# PowCarbinBoard_Isolation.net
KiCad netlist of a schematic drawn in Altium Designer
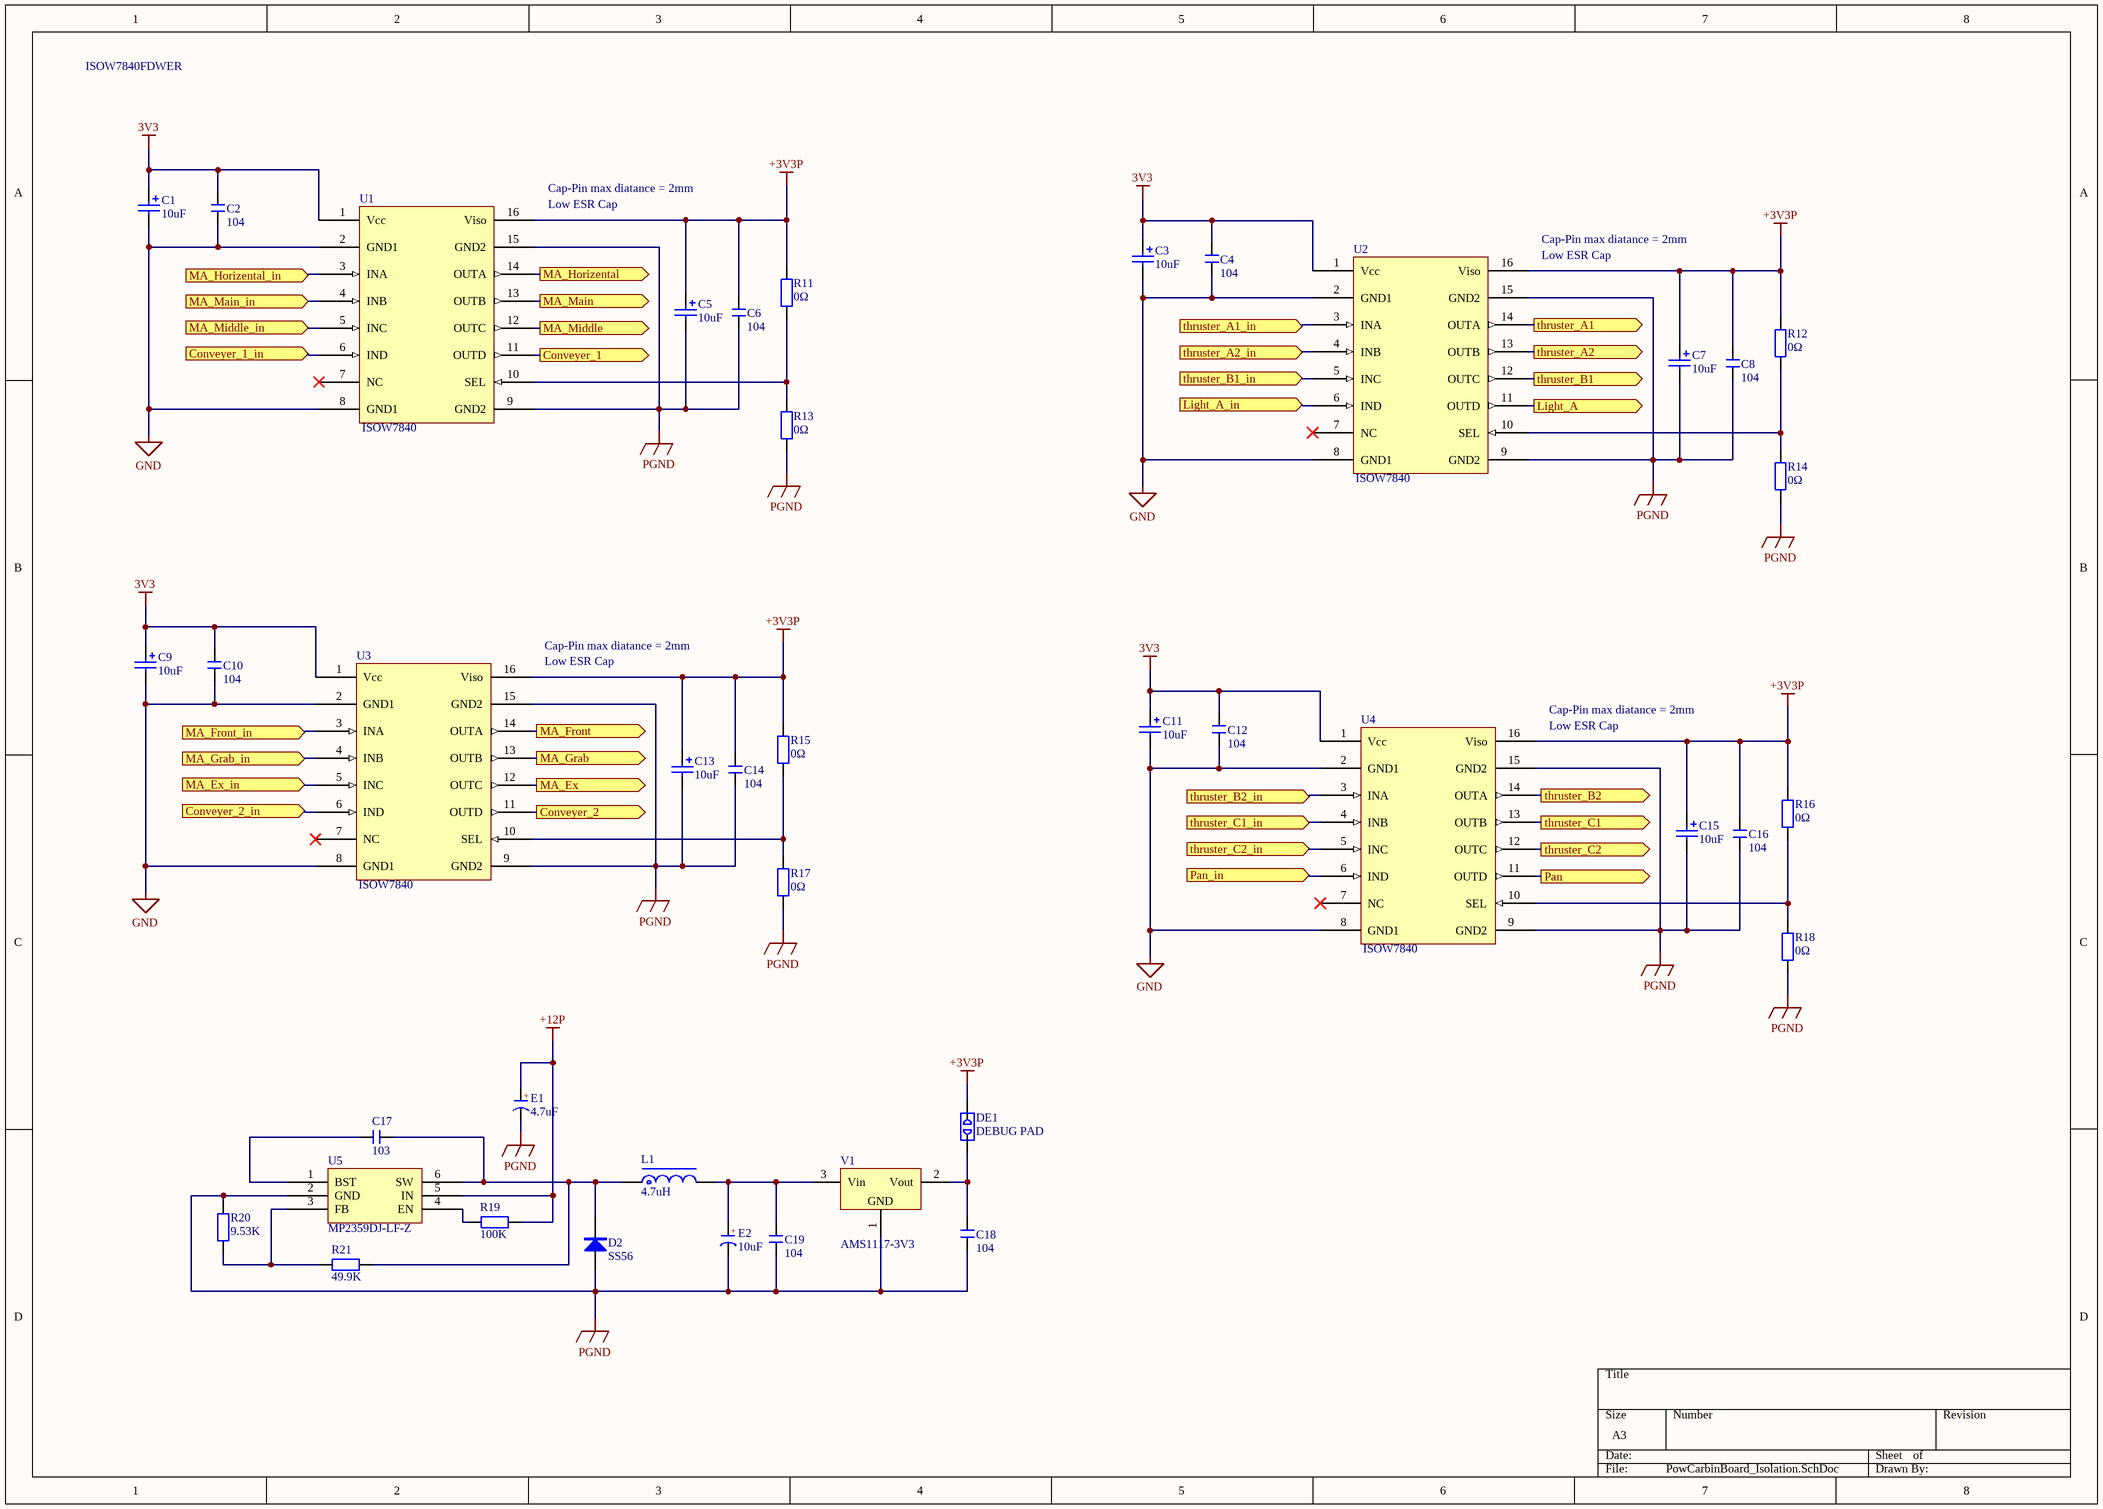
[diagram p0: PowCarbinBoard_Isolation.SchDoc]

(export (version "E")
  (design (tool "Eeschema 10.0.6"))
  (components
    (comp (ref "C1")
      (value "10uF")
      (footprint "CASE-B_3528")
      (description "钽电容")
      (libsource (lib "Miscellaneous Devices LC") (part "3528 100uF (107) 10% 6.3V"))
    )
    (comp (ref "C2")
      (value "104")
      (footprint "C 0603_L")
      (description "无极性贴片电容")
      (fields (field (name "版权归属") "源创客"))
      (libsource (lib "3.1   - 电阻-电容-电感") (part "C"))
    )
    (comp (ref "C3")
      (value "10uF")
      (footprint "CASE-B_3528")
      (description "钽电容")
      (libsource (lib "Miscellaneous Devices LC") (part "3528 100uF (107) 10% 6.3V"))
    )
    (comp (ref "C4")
      (value "104")
      (footprint "C 0603_L")
      (description "无极性贴片电容")
      (fields (field (name "版权归属") "源创客"))
      (libsource (lib "3.1   - 电阻-电容-电感") (part "C"))
    )
    (comp (ref "C5")
      (value "10uF")
      (footprint "CASE-B_3528")
      (description "钽电容")
      (libsource (lib "Miscellaneous Devices LC") (part "3528 100uF (107) 10% 6.3V"))
    )
    (comp (ref "C6")
      (value "104")
      (footprint "C 0603_L")
      (description "无极性贴片电容")
      (fields (field (name "版权归属") "源创客"))
      (libsource (lib "3.1   - 电阻-电容-电感") (part "C"))
    )
    (comp (ref "C7")
      (value "10uF")
      (footprint "CASE-B_3528")
      (description "钽电容")
      (libsource (lib "Miscellaneous Devices LC") (part "3528 100uF (107) 10% 6.3V"))
    )
    (comp (ref "C8")
      (value "104")
      (footprint "C 0603_L")
      (description "无极性贴片电容")
      (fields (field (name "版权归属") "源创客"))
      (libsource (lib "3.1   - 电阻-电容-电感") (part "C"))
    )
    (comp (ref "C9")
      (value "10uF")
      (footprint "CASE-B_3528")
      (description "钽电容")
      (libsource (lib "Miscellaneous Devices LC") (part "3528 100uF (107) 10% 6.3V"))
    )
    (comp (ref "C10")
      (value "104")
      (footprint "C 0603_L")
      (description "无极性贴片电容")
      (fields (field (name "版权归属") "源创客"))
      (libsource (lib "3.1   - 电阻-电容-电感") (part "C"))
    )
    (comp (ref "C11")
      (value "10uF")
      (footprint "CASE-B_3528")
      (description "钽电容")
      (libsource (lib "Miscellaneous Devices LC") (part "3528 100uF (107) 10% 6.3V"))
    )
    (comp (ref "C12")
      (value "104")
      (footprint "C 0603_L")
      (description "无极性贴片电容")
      (fields (field (name "版权归属") "源创客"))
      (libsource (lib "3.1   - 电阻-电容-电感") (part "C"))
    )
    (comp (ref "C13")
      (value "10uF")
      (footprint "CASE-B_3528")
      (description "钽电容")
      (libsource (lib "Miscellaneous Devices LC") (part "3528 100uF (107) 10% 6.3V"))
    )
    (comp (ref "C14")
      (value "104")
      (footprint "C 0603_L")
      (description "无极性贴片电容")
      (fields (field (name "版权归属") "源创客"))
      (libsource (lib "3.1   - 电阻-电容-电感") (part "C"))
    )
    (comp (ref "C15")
      (value "10uF")
      (footprint "CASE-B_3528")
      (description "钽电容")
      (libsource (lib "Miscellaneous Devices LC") (part "3528 100uF (107) 10% 6.3V"))
    )
    (comp (ref "C16")
      (value "104")
      (footprint "C 0603_L")
      (description "无极性贴片电容")
      (fields (field (name "版权归属") "源创客"))
      (libsource (lib "3.1   - 电阻-电容-电感") (part "C"))
    )
    (comp (ref "C17")
      (value "103")
      (footprint "C 0603_L")
      (description "无极性贴片电容")
      (fields (field (name "版权归属") "源创客"))
      (libsource (lib "3.1   - 电阻-电容-电感") (part "C"))
    )
    (comp (ref "C18")
      (value "104")
      (footprint "C 0603_L")
      (description "无极性贴片电容")
      (fields (field (name "版权归属") "源创客"))
      (libsource (lib "3.1   - 电阻-电容-电感") (part "C"))
    )
    (comp (ref "C19")
      (value "104")
      (footprint "C 0603_L")
      (description "无极性贴片电容")
      (fields (field (name "版权归属") "源创客"))
      (libsource (lib "3.1   - 电阻-电容-电感") (part "C"))
    )
    (comp (ref "D2")
      (value "SS56")
      (footprint "SMA")
      (description "肖特基二极管")
      (fields (field (name "版权归属") "源创客"))
      (libsource (lib "8.1   - 二极管-整流桥") (part "SS14"))
    )
    (comp (ref "DE1")
      (value "DEBUG PAD")
      (footprint "DEBUG_A")
      (description "调试断点焊盘")
      (fields (field (name "版权归属") "源创客"))
      (libsource (lib "15.1 - 未分类器件") (part "DEBUG"))
    )
    (comp (ref "E1")
      (value "4.7uF")
      (footprint "CM B(4*5.4)")
      (description "贴片电解电容")
      (fields (field (name "版权归属") "源创客"))
      (libsource (lib "3.1   - 电阻-电容-电感") (part "C-CM"))
    )
    (comp (ref "E2")
      (value "10uF")
      (footprint "CM B(4*5.4)")
      (description "贴片电解电容")
      (fields (field (name "版权归属") "源创客"))
      (libsource (lib "3.1   - 电阻-电容-电感") (part "C-CM"))
    )
    (comp (ref "L1")
      (value "4.7uH")
      (footprint "CDRH74")
      (description "功率屏蔽电感")
      (fields (field (name "版权归属") "源创客"))
      (libsource (lib "3.1   - 电阻-电容-电感") (part "L-CDRH"))
    )
    (comp (ref "R11")
      (value "0Ω")
      (footprint "R 0603_L")
      (description "贴片电阻")
      (fields (field (name "版权归属") "源创客"))
      (libsource (lib "3.1   - 电阻-电容-电感") (part "R"))
    )
    (comp (ref "R12")
      (value "0Ω")
      (footprint "R 0603_L")
      (description "贴片电阻")
      (fields (field (name "版权归属") "源创客"))
      (libsource (lib "3.1   - 电阻-电容-电感") (part "R"))
    )
    (comp (ref "R13")
      (value "0Ω")
      (footprint "R 0603_L")
      (description "贴片电阻")
      (fields (field (name "版权归属") "源创客"))
      (libsource (lib "3.1   - 电阻-电容-电感") (part "R"))
    )
    (comp (ref "R14")
      (value "0Ω")
      (footprint "R 0603_L")
      (description "贴片电阻")
      (fields (field (name "版权归属") "源创客"))
      (libsource (lib "3.1   - 电阻-电容-电感") (part "R"))
    )
    (comp (ref "R15")
      (value "0Ω")
      (footprint "R 0603_L")
      (description "贴片电阻")
      (fields (field (name "版权归属") "源创客"))
      (libsource (lib "3.1   - 电阻-电容-电感") (part "R"))
    )
    (comp (ref "R16")
      (value "0Ω")
      (footprint "R 0603_L")
      (description "贴片电阻")
      (fields (field (name "版权归属") "源创客"))
      (libsource (lib "3.1   - 电阻-电容-电感") (part "R"))
    )
    (comp (ref "R17")
      (value "0Ω")
      (footprint "R 0603_L")
      (description "贴片电阻")
      (fields (field (name "版权归属") "源创客"))
      (libsource (lib "3.1   - 电阻-电容-电感") (part "R"))
    )
    (comp (ref "R18")
      (value "0Ω")
      (footprint "R 0603_L")
      (description "贴片电阻")
      (fields (field (name "版权归属") "源创客"))
      (libsource (lib "3.1   - 电阻-电容-电感") (part "R"))
    )
    (comp (ref "R19")
      (value "100K")
      (footprint "R 0603_L")
      (description "贴片电阻")
      (fields (field (name "版权归属") "源创客"))
      (libsource (lib "3.1   - 电阻-电容-电感") (part "R"))
    )
    (comp (ref "R20")
      (value "9.53K")
      (footprint "R 0603_L")
      (description "贴片电阻")
      (fields (field (name "版权归属") "源创客"))
      (libsource (lib "3.1   - 电阻-电容-电感") (part "R"))
    )
    (comp (ref "R21")
      (value "49.9K")
      (footprint "R 0603_L")
      (description "贴片电阻")
      (fields (field (name "版权归属") "源创客"))
      (libsource (lib "3.1   - 电阻-电容-电感") (part "R"))
    )
    (comp (ref "U1") (value "ISOW7840") (footprint "ISOW7840") (libsource (lib "Schlib1") (part "ISOW7840")))
    (comp (ref "U2") (value "ISOW7840") (footprint "ISOW7840") (libsource (lib "Schlib1") (part "ISOW7840")))
    (comp (ref "U3") (value "ISOW7840") (footprint "ISOW7840") (libsource (lib "Schlib1") (part "ISOW7840")))
    (comp (ref "U4") (value "ISOW7840") (footprint "ISOW7840") (libsource (lib "Schlib1") (part "ISOW7840")))
    (comp (ref "U5")
      (value "MP2359DJ-LF-Z")
      (footprint "SOT-23-6")
      (description "DC-DC芯片")
      (libsource (lib "Miscellaneous Devices LC") (part "MP2359DJ-LF-Z_[C14259]"))
    )
    (comp (ref "V1")
      (value "AMS1117-3V3")
      (footprint "SOT89_N")
      (description "三端稳压芯片")
      (fields (field (name "版权归属") "源创客"))
      (libsource (lib "1.3   - 电源类芯片") (part "AMS1117"))
    )
  )
  (nets
    (net (code "1") (name "+3V3P") (class "Default")
      (node (ref "C13") (pin "1") (pinfunction "1_1") (pintype "passive"))
      (node (ref "C14") (pin "2") (pinfunction "2_2") (pintype "passive"))
      (node (ref "C15") (pin "1") (pinfunction "1_1") (pintype "passive"))
      (node (ref "C16") (pin "2") (pinfunction "2_2") (pintype "passive"))
      (node (ref "C5") (pin "1") (pinfunction "1_1") (pintype "passive"))
      (node (ref "C6") (pin "2") (pinfunction "2_2") (pintype "passive"))
      (node (ref "C7") (pin "1") (pinfunction "1_1") (pintype "passive"))
      (node (ref "C8") (pin "2") (pinfunction "2_2") (pintype "passive"))
      (node (ref "DE1") (pin "2") (pinfunction "2_2") (pintype "passive"))
      (node (ref "R11") (pin "2") (pinfunction "2_2") (pintype "passive"))
      (node (ref "R12") (pin "2") (pinfunction "2_2") (pintype "passive"))
      (node (ref "R15") (pin "2") (pinfunction "2_2") (pintype "passive"))
      (node (ref "R16") (pin "2") (pinfunction "2_2") (pintype "passive"))
      (node (ref "U1") (pin "16") (pinfunction "Viso_16") (pintype "power_in"))
      (node (ref "U2") (pin "16") (pinfunction "Viso_16") (pintype "power_in"))
      (node (ref "U3") (pin "16") (pinfunction "Viso_16") (pintype "power_in"))
      (node (ref "U4") (pin "16") (pinfunction "Viso_16") (pintype "power_in"))
    )
    (net (code "2") (name "+12P") (class "Default")
      (node (ref "E1") (pin "1") (pinfunction "A_1") (pintype "passive"))
      (node (ref "R19") (pin "1") (pinfunction "1_1") (pintype "passive"))
      (node (ref "U5") (pin "5") (pinfunction "IN_5") (pintype "passive"))
    )
    (net (code "3") (name "/Conveyer_1") (class "Default")
      (node (ref "U1") (pin "11") (pinfunction "OUTD_11") (pintype "output"))
    )
    (net (code "4") (name "/Conveyer_1_in") (class "Default")
      (node (ref "U1") (pin "6") (pinfunction "IND_6") (pintype "input"))
    )
    (net (code "5") (name "/Conveyer_2") (class "Default")
      (node (ref "U3") (pin "11") (pinfunction "OUTD_11") (pintype "output"))
    )
    (net (code "6") (name "/Conveyer_2_in") (class "Default")
      (node (ref "U3") (pin "6") (pinfunction "IND_6") (pintype "input"))
    )
    (net (code "7") (name "/Light_A") (class "Default")
      (node (ref "U2") (pin "11") (pinfunction "OUTD_11") (pintype "output"))
    )
    (net (code "8") (name "/Light_A_in") (class "Default")
      (node (ref "U2") (pin "6") (pinfunction "IND_6") (pintype "input"))
    )
    (net (code "9") (name "/MA_Ex") (class "Default")
      (node (ref "U3") (pin "12") (pinfunction "OUTC_12") (pintype "output"))
    )
    (net (code "10") (name "/MA_Ex_in") (class "Default")
      (node (ref "U3") (pin "5") (pinfunction "INC_5") (pintype "input"))
    )
    (net (code "11") (name "/MA_Front") (class "Default")
      (node (ref "U3") (pin "14") (pinfunction "OUTA_14") (pintype "output"))
    )
    (net (code "12") (name "/MA_Front_in") (class "Default")
      (node (ref "U3") (pin "3") (pinfunction "INA_3") (pintype "input"))
    )
    (net (code "13") (name "/MA_Grab") (class "Default")
      (node (ref "U3") (pin "13") (pinfunction "OUTB_13") (pintype "output"))
    )
    (net (code "14") (name "/MA_Grab_in") (class "Default")
      (node (ref "U3") (pin "4") (pinfunction "INB_4") (pintype "input"))
    )
    (net (code "15") (name "/MA_Horizental") (class "Default")
      (node (ref "U1") (pin "14") (pinfunction "OUTA_14") (pintype "output"))
    )
    (net (code "16") (name "/MA_Horizental_in") (class "Default")
      (node (ref "U1") (pin "3") (pinfunction "INA_3") (pintype "input"))
    )
    (net (code "17") (name "/MA_Main") (class "Default")
      (node (ref "U1") (pin "13") (pinfunction "OUTB_13") (pintype "output"))
    )
    (net (code "18") (name "/MA_Main_in") (class "Default")
      (node (ref "U1") (pin "4") (pinfunction "INB_4") (pintype "input"))
    )
    (net (code "19") (name "/MA_Middle") (class "Default")
      (node (ref "U1") (pin "12") (pinfunction "OUTC_12") (pintype "output"))
    )
    (net (code "20") (name "/MA_Middle_in") (class "Default")
      (node (ref "U1") (pin "5") (pinfunction "INC_5") (pintype "input"))
    )
    (net (code "21") (name "/Pan") (class "Default")
      (node (ref "U4") (pin "11") (pinfunction "OUTD_11") (pintype "output"))
    )
    (net (code "22") (name "/Pan_in") (class "Default")
      (node (ref "U4") (pin "6") (pinfunction "IND_6") (pintype "input"))
    )
    (net (code "23") (name "/thruster_A1") (class "Default")
      (node (ref "U2") (pin "14") (pinfunction "OUTA_14") (pintype "output"))
    )
    (net (code "24") (name "/thruster_A1_in") (class "Default")
      (node (ref "U2") (pin "3") (pinfunction "INA_3") (pintype "input"))
    )
    (net (code "25") (name "/thruster_A2") (class "Default")
      (node (ref "U2") (pin "13") (pinfunction "OUTB_13") (pintype "output"))
    )
    (net (code "26") (name "/thruster_A2_in") (class "Default")
      (node (ref "U2") (pin "4") (pinfunction "INB_4") (pintype "input"))
    )
    (net (code "27") (name "/thruster_B1") (class "Default")
      (node (ref "U2") (pin "12") (pinfunction "OUTC_12") (pintype "output"))
    )
    (net (code "28") (name "/thruster_B1_in") (class "Default")
      (node (ref "U2") (pin "5") (pinfunction "INC_5") (pintype "input"))
    )
    (net (code "29") (name "/thruster_B2") (class "Default")
      (node (ref "U4") (pin "14") (pinfunction "OUTA_14") (pintype "output"))
    )
    (net (code "30") (name "/thruster_B2_in") (class "Default")
      (node (ref "U4") (pin "3") (pinfunction "INA_3") (pintype "input"))
    )
    (net (code "31") (name "/thruster_C1") (class "Default")
      (node (ref "U4") (pin "13") (pinfunction "OUTB_13") (pintype "output"))
    )
    (net (code "32") (name "/thruster_C1_in") (class "Default")
      (node (ref "U4") (pin "4") (pinfunction "INB_4") (pintype "input"))
    )
    (net (code "33") (name "/thruster_C2") (class "Default")
      (node (ref "U4") (pin "12") (pinfunction "OUTC_12") (pintype "output"))
    )
    (net (code "34") (name "/thruster_C2_in") (class "Default")
      (node (ref "U4") (pin "5") (pinfunction "INC_5") (pintype "input"))
    )
    (net (code "35") (name "3V3") (class "Default")
      (node (ref "C1") (pin "1") (pinfunction "1_1") (pintype "passive"))
      (node (ref "C10") (pin "2") (pinfunction "2_2") (pintype "passive"))
      (node (ref "C11") (pin "1") (pinfunction "1_1") (pintype "passive"))
      (node (ref "C12") (pin "2") (pinfunction "2_2") (pintype "passive"))
      (node (ref "C2") (pin "2") (pinfunction "2_2") (pintype "passive"))
      (node (ref "C3") (pin "1") (pinfunction "1_1") (pintype "passive"))
      (node (ref "C4") (pin "2") (pinfunction "2_2") (pintype "passive"))
      (node (ref "C9") (pin "1") (pinfunction "1_1") (pintype "passive"))
      (node (ref "U1") (pin "1") (pinfunction "Vcc_1") (pintype "power_in"))
      (node (ref "U2") (pin "1") (pinfunction "Vcc_1") (pintype "power_in"))
      (node (ref "U3") (pin "1") (pinfunction "Vcc_1") (pintype "power_in"))
      (node (ref "U4") (pin "1") (pinfunction "Vcc_1") (pintype "power_in"))
    )
    (net (code "36") (name "GND") (class "Default")
      (node (ref "C1") (pin "2") (pinfunction "2_2") (pintype "passive"))
      (node (ref "C10") (pin "1") (pinfunction "1_1") (pintype "passive"))
      (node (ref "C11") (pin "2") (pinfunction "2_2") (pintype "passive"))
      (node (ref "C12") (pin "1") (pinfunction "1_1") (pintype "passive"))
      (node (ref "C2") (pin "1") (pinfunction "1_1") (pintype "passive"))
      (node (ref "C3") (pin "2") (pinfunction "2_2") (pintype "passive"))
      (node (ref "C4") (pin "1") (pinfunction "1_1") (pintype "passive"))
      (node (ref "C9") (pin "2") (pinfunction "2_2") (pintype "passive"))
      (node (ref "U1") (pin "2") (pinfunction "GND1_2") (pintype "power_in"))
      (node (ref "U1") (pin "8") (pinfunction "GND1_8") (pintype "power_in"))
      (node (ref "U2") (pin "2") (pinfunction "GND1_2") (pintype "power_in"))
      (node (ref "U2") (pin "8") (pinfunction "GND1_8") (pintype "power_in"))
      (node (ref "U3") (pin "2") (pinfunction "GND1_2") (pintype "power_in"))
      (node (ref "U3") (pin "8") (pinfunction "GND1_8") (pintype "power_in"))
      (node (ref "U4") (pin "2") (pinfunction "GND1_2") (pintype "power_in"))
      (node (ref "U4") (pin "8") (pinfunction "GND1_8") (pintype "power_in"))
    )
    (net (code "37") (name "Net-(D2-K)") (class "Default")
      (node (ref "C17") (pin "1") (pinfunction "1_1") (pintype "passive"))
      (node (ref "D2") (pin "2") (pinfunction "K_2") (pintype "passive"))
      (node (ref "L1") (pin "1") (pinfunction "1_1") (pintype "passive"))
      (node (ref "R21") (pin "2") (pinfunction "2_2") (pintype "passive"))
      (node (ref "U5") (pin "6") (pinfunction "SW_6") (pintype "passive"))
    )
    (net (code "38") (name "Net-(E2-A)") (class "Default")
      (node (ref "C19") (pin "2") (pinfunction "2_2") (pintype "passive"))
      (node (ref "E2") (pin "1") (pinfunction "A_1") (pintype "passive"))
      (node (ref "L1") (pin "2") (pinfunction "2_2") (pintype "passive"))
      (node (ref "V1") (pin "3") (pinfunction "Vin_3") (pintype "passive"))
    )
    (net (code "39") (name "Net-(U1-SEL)") (class "Default")
      (node (ref "R11") (pin "1") (pinfunction "1_1") (pintype "passive"))
      (node (ref "R13") (pin "2") (pinfunction "2_2") (pintype "passive"))
      (node (ref "U1") (pin "10") (pinfunction "SEL_10") (pintype "input"))
    )
    (net (code "40") (name "Net-(U2-SEL)") (class "Default")
      (node (ref "R12") (pin "1") (pinfunction "1_1") (pintype "passive"))
      (node (ref "R14") (pin "2") (pinfunction "2_2") (pintype "passive"))
      (node (ref "U2") (pin "10") (pinfunction "SEL_10") (pintype "input"))
    )
    (net (code "41") (name "Net-(U3-SEL)") (class "Default")
      (node (ref "R15") (pin "1") (pinfunction "1_1") (pintype "passive"))
      (node (ref "R17") (pin "2") (pinfunction "2_2") (pintype "passive"))
      (node (ref "U3") (pin "10") (pinfunction "SEL_10") (pintype "input"))
    )
    (net (code "42") (name "Net-(U4-SEL)") (class "Default")
      (node (ref "R16") (pin "1") (pinfunction "1_1") (pintype "passive"))
      (node (ref "R18") (pin "2") (pinfunction "2_2") (pintype "passive"))
      (node (ref "U4") (pin "10") (pinfunction "SEL_10") (pintype "input"))
    )
    (net (code "43") (name "Net-(U5-BST)") (class "Default")
      (node (ref "C17") (pin "2") (pinfunction "2_2") (pintype "passive"))
      (node (ref "U5") (pin "1") (pinfunction "BST_1") (pintype "passive"))
    )
    (net (code "44") (name "Net-(U5-EN)") (class "Default")
      (node (ref "R19") (pin "2") (pinfunction "2_2") (pintype "passive"))
      (node (ref "U5") (pin "4") (pinfunction "EN_4") (pintype "passive"))
    )
    (net (code "45") (name "Net-(U5-FB)") (class "Default")
      (node (ref "R20") (pin "1") (pinfunction "1_1") (pintype "passive"))
      (node (ref "R21") (pin "1") (pinfunction "1_1") (pintype "passive"))
      (node (ref "U5") (pin "3") (pinfunction "FB_3") (pintype "passive"))
    )
    (net (code "46") (name "Net-(V1-Vout)") (class "Default")
      (node (ref "C18") (pin "2") (pinfunction "2_2") (pintype "passive"))
      (node (ref "DE1") (pin "1") (pinfunction "1_1") (pintype "passive"))
      (node (ref "V1") (pin "2") (pinfunction "Vout_2") (pintype "passive"))
    )
    (net (code "47") (name "PGND") (class "Default")
      (node (ref "C13") (pin "2") (pinfunction "2_2") (pintype "passive"))
      (node (ref "C14") (pin "1") (pinfunction "1_1") (pintype "passive"))
      (node (ref "C15") (pin "2") (pinfunction "2_2") (pintype "passive"))
      (node (ref "C16") (pin "1") (pinfunction "1_1") (pintype "passive"))
      (node (ref "C18") (pin "1") (pinfunction "1_1") (pintype "passive"))
      (node (ref "C19") (pin "1") (pinfunction "1_1") (pintype "passive"))
      (node (ref "C5") (pin "2") (pinfunction "2_2") (pintype "passive"))
      (node (ref "C6") (pin "1") (pinfunction "1_1") (pintype "passive"))
      (node (ref "C7") (pin "2") (pinfunction "2_2") (pintype "passive"))
      (node (ref "C8") (pin "1") (pinfunction "1_1") (pintype "passive"))
      (node (ref "D2") (pin "1") (pinfunction "A_1") (pintype "passive"))
      (node (ref "E1") (pin "2") (pinfunction "K_2") (pintype "passive"))
      (node (ref "E2") (pin "2") (pinfunction "K_2") (pintype "passive"))
      (node (ref "R13") (pin "1") (pinfunction "1_1") (pintype "passive"))
      (node (ref "R14") (pin "1") (pinfunction "1_1") (pintype "passive"))
      (node (ref "R17") (pin "1") (pinfunction "1_1") (pintype "passive"))
      (node (ref "R18") (pin "1") (pinfunction "1_1") (pintype "passive"))
      (node (ref "R20") (pin "2") (pinfunction "2_2") (pintype "passive"))
      (node (ref "U1") (pin "15") (pinfunction "GND2_15") (pintype "power_in"))
      (node (ref "U1") (pin "9") (pinfunction "GND2_9") (pintype "power_in"))
      (node (ref "U2") (pin "15") (pinfunction "GND2_15") (pintype "power_in"))
      (node (ref "U2") (pin "9") (pinfunction "GND2_9") (pintype "power_in"))
      (node (ref "U3") (pin "15") (pinfunction "GND2_15") (pintype "power_in"))
      (node (ref "U3") (pin "9") (pinfunction "GND2_9") (pintype "power_in"))
      (node (ref "U4") (pin "15") (pinfunction "GND2_15") (pintype "power_in"))
      (node (ref "U4") (pin "9") (pinfunction "GND2_9") (pintype "power_in"))
      (node (ref "U5") (pin "2") (pinfunction "GND_2") (pintype "passive"))
      (node (ref "V1") (pin "1") (pinfunction "GND_1") (pintype "passive"))
    )
    (net (code "48") (name "unconnected-(U1-NC-Pad7)") (class "Default")
      (node (ref "U1") (pin "7") (pinfunction "NC_7") (pintype "passive+no_connect"))
    )
    (net (code "49") (name "unconnected-(U2-NC-Pad7)") (class "Default")
      (node (ref "U2") (pin "7") (pinfunction "NC_7") (pintype "passive+no_connect"))
    )
    (net (code "50") (name "unconnected-(U3-NC-Pad7)") (class "Default")
      (node (ref "U3") (pin "7") (pinfunction "NC_7") (pintype "passive+no_connect"))
    )
    (net (code "51") (name "unconnected-(U4-NC-Pad7)") (class "Default")
      (node (ref "U4") (pin "7") (pinfunction "NC_7") (pintype "passive+no_connect"))
    )
  )
)
